# -.net
KiCad netlist of a schematic drawn in Altium Designer
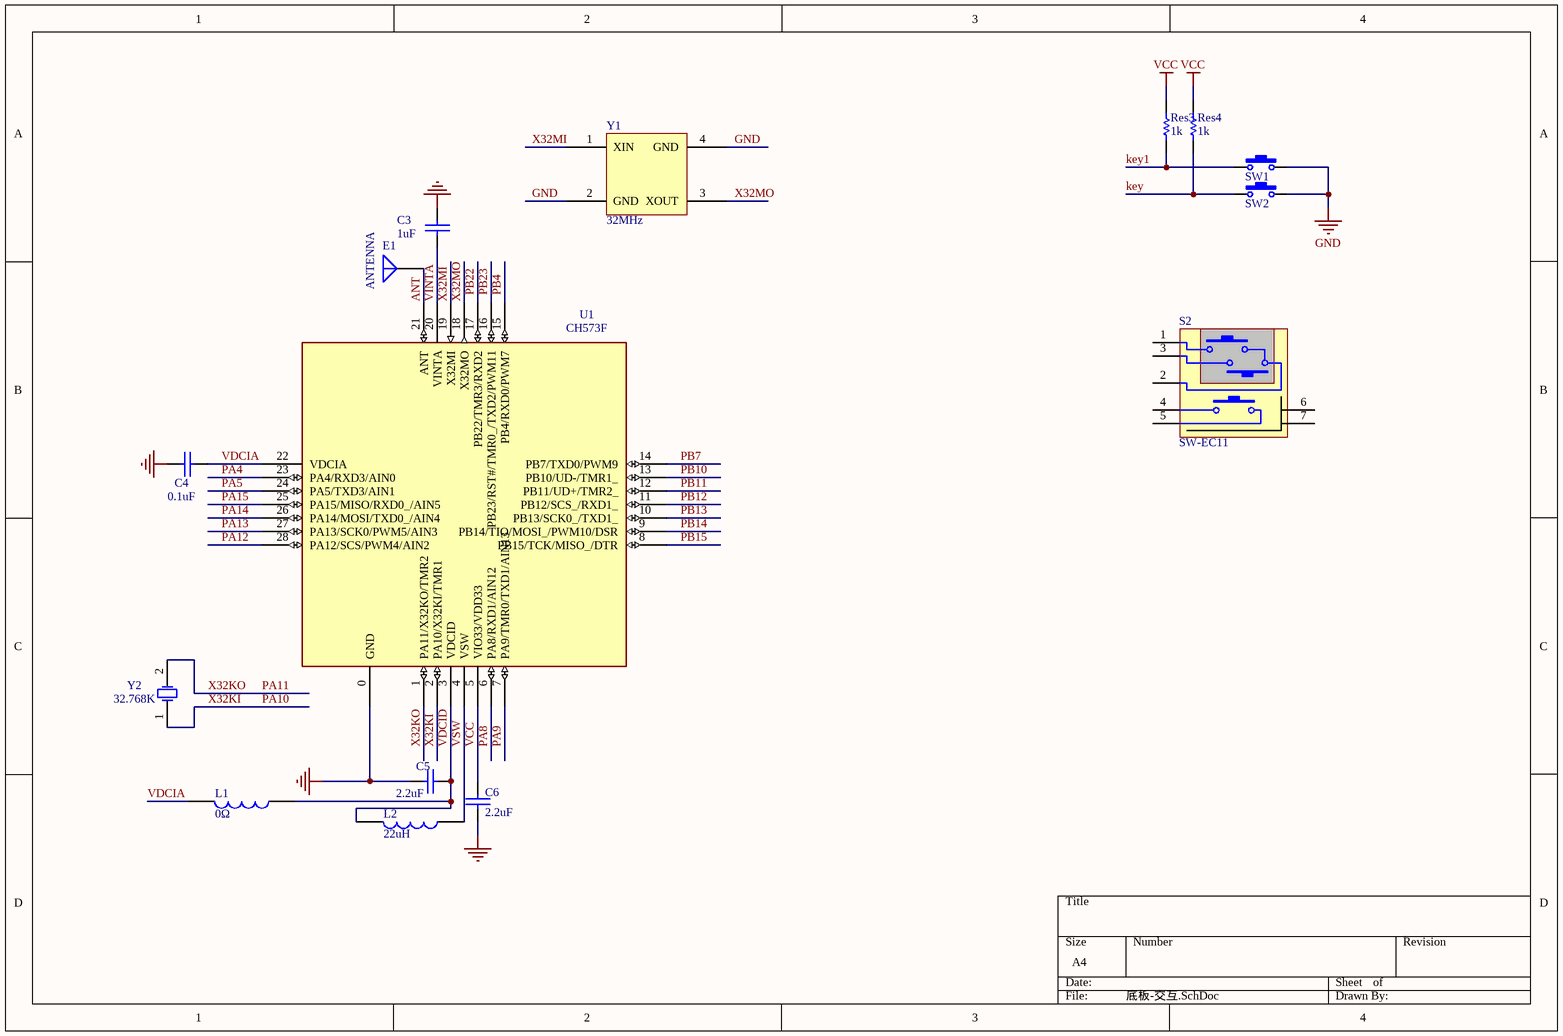
[diagram p0: 底板-交互.SchDoc]

(export (version "E")
  (design (tool "Eeschema 10.0.6"))
  (components
    (comp (ref "C3")
      (value "1uF")
      (footprint "MYPCB:0402")
      (description "Capacitor")
      (libsource (lib "*") (part "CAP"))
    )
    (comp (ref "C4")
      (value "0.1uF")
      (footprint "MYPCB:0402")
      (description "Capacitor")
      (libsource (lib "*") (part "CAP"))
    )
    (comp (ref "C5")
      (value "2.2uF")
      (footprint "MYPCB:0402")
      (description "Capacitor")
      (libsource (lib "*") (part "CAP"))
    )
    (comp (ref "C6")
      (value "2.2uF")
      (footprint "MYPCB:0402")
      (description "Capacitor")
      (libsource (lib "*") (part "CAP"))
    )
    (comp (ref "E1")
      (value "ANTENNA")
      (footprint "ANT-F-1-2.4G-1.6")
      (description "Generic Antenna")
      (libsource (lib "*") (part "ANTENNA"))
    )
    (comp (ref "L1") (value "0Ω") (footprint "0603") (libsource (lib "*") (part "INDUCTOR")))
    (comp (ref "L2") (value "22uH") (footprint "L2.2") (libsource (lib "*") (part "INDUCTOR")))
    (comp (ref "Res3") (value "1k") (footprint "0805R") (libsource (lib "电阻") (part "RES")))
    (comp (ref "Res4") (value "1k") (footprint "0805R") (libsource (lib "电阻") (part "RES")))
    (comp (ref "S2")
      (value "SW-EC11")
      (footprint "EC11")
      (description "旋转编码开关")
      (libsource (lib "0.7 - 常用按键-开关-蜂鸣器-电池-测试点") (part "SW-EC11"))
    )
    (comp (ref "SW1")
      (value "3x6x5")
      (footprint "SW 3*6*4.3-S-W")
      (description "3x6轻触开关")
      (libsource (lib "0.7 - 常用按键-开关-蜂鸣器-电池-测试点") (part "TSW 3x6"))
    )
    (comp (ref "SW2")
      (value "3x6x5")
      (footprint "SW 3*6*4.3-S-W")
      (description "3x6轻触开关")
      (libsource (lib "0.7 - 常用按键-开关-蜂鸣器-电池-测试点") (part "TSW 3x6"))
    )
    (comp (ref "U1")
      (value "CH573F")
      (footprint "QFN28_4X4")
      (description "RISC-V MCU with BLE/USB/ADC/SPI/4*UART")
      (libsource (lib "altium-import") (part "root_0_CH573F_"))
    )
    (comp (ref "Y1") (value "32MHz") (footprint "3225") (libsource (lib "wch_sch_others") (part "晶体")))
    (comp (ref "Y2")
      (value "32.768K")
      (footprint "fc-135")
      (description "Crystal Oscillator")
      (fields (field (name "PUBLISHER") "Altium Limited"))
      (libsource (lib "*") (part "XTAL"))
    )
  )
  (nets
    (net (code "1") (name "/ANT") (class "Default")
      (node (ref "E1") (pin "1") (pinfunction "A_1") (pintype "passive"))
      (node (ref "U1") (pin "21") (pinfunction "ANT_21") (pintype "bidirectional"))
    )
    (net (code "2") (name "/PA4") (class "Default")
      (node (ref "U1") (pin "23") (pinfunction "PA4/RXD3/AIN0_23") (pintype "bidirectional"))
    )
    (net (code "3") (name "/PA5") (class "Default")
      (node (ref "U1") (pin "24") (pinfunction "PA5/TXD3/AIN1_24") (pintype "bidirectional"))
    )
    (net (code "4") (name "/PA8") (class "Default")
      (node (ref "U1") (pin "6") (pinfunction "PA8/RXD1/AIN12_6") (pintype "bidirectional"))
    )
    (net (code "5") (name "/PA9") (class "Default")
      (node (ref "U1") (pin "7") (pinfunction "PA9/TMR0/TXD1/AIN13_7") (pintype "bidirectional"))
    )
    (net (code "6") (name "/PA10") (class "Default")
      (node (ref "U1") (pin "2") (pinfunction "PA10/X32KI/TMR1_2") (pintype "bidirectional"))
      (node (ref "Y2") (pin "1") (pinfunction "OSC1_1") (pintype "passive"))
    )
    (net (code "7") (name "/PA11") (class "Default")
      (node (ref "U1") (pin "1") (pinfunction "PA11/X32KO/TMR2_1") (pintype "bidirectional"))
      (node (ref "Y2") (pin "2") (pinfunction "OSC2_2") (pintype "passive"))
    )
    (net (code "8") (name "/PA12") (class "Default")
      (node (ref "U1") (pin "28") (pinfunction "PA12/SCS/PWM4/AIN2_28") (pintype "bidirectional"))
    )
    (net (code "9") (name "/PA13") (class "Default")
      (node (ref "U1") (pin "27") (pinfunction "PA13/SCK0/PWM5/AIN3_27") (pintype "bidirectional"))
    )
    (net (code "10") (name "/PA14") (class "Default")
      (node (ref "U1") (pin "26") (pinfunction "PA14/MOSI/TXD0_/AIN4_26") (pintype "bidirectional"))
    )
    (net (code "11") (name "/PA15") (class "Default")
      (node (ref "U1") (pin "25") (pinfunction "PA15/MISO/RXD0_/AIN5_25") (pintype "bidirectional"))
    )
    (net (code "12") (name "/PB4") (class "Default")
      (node (ref "U1") (pin "15") (pinfunction "PB4/RXD0/PWM7_15") (pintype "bidirectional"))
    )
    (net (code "13") (name "/PB7") (class "Default")
      (node (ref "U1") (pin "14") (pinfunction "PB7/TXD0/PWM9_14") (pintype "bidirectional"))
    )
    (net (code "14") (name "/PB10") (class "Default")
      (node (ref "U1") (pin "13") (pinfunction "PB10/UD-/TMR1__13") (pintype "bidirectional"))
    )
    (net (code "15") (name "/PB11") (class "Default")
      (node (ref "U1") (pin "12") (pinfunction "PB11/UD+/TMR2__12") (pintype "bidirectional"))
    )
    (net (code "16") (name "/PB12") (class "Default")
      (node (ref "U1") (pin "11") (pinfunction "PB12/SCS_/RXD1__11") (pintype "bidirectional"))
    )
    (net (code "17") (name "/PB13") (class "Default")
      (node (ref "U1") (pin "10") (pinfunction "PB13/SCK0_/TXD1__10") (pintype "bidirectional"))
    )
    (net (code "18") (name "/PB14") (class "Default")
      (node (ref "U1") (pin "9") (pinfunction "PB14/TIO/MOSI_/PWM10/DSR_9") (pintype "bidirectional"))
    )
    (net (code "19") (name "/PB15") (class "Default")
      (node (ref "U1") (pin "8") (pinfunction "PB15/TCK/MISO_/DTR_8") (pintype "bidirectional"))
    )
    (net (code "20") (name "/PB22") (class "Default")
      (node (ref "U1") (pin "17") (pinfunction "PB22/TMR3/RXD2_17") (pintype "bidirectional"))
    )
    (net (code "21") (name "/PB23") (class "Default")
      (node (ref "U1") (pin "16") (pinfunction "PB23/RST#/TMR0_/TXD2/PWM11_16") (pintype "bidirectional"))
    )
    (net (code "22") (name "/VDCIA") (class "Default")
      (node (ref "C4") (pin "1") (pinfunction "1_1") (pintype "passive"))
      (node (ref "L1") (pin "2") (pinfunction "2_2") (pintype "passive"))
      (node (ref "U1") (pin "22") (pinfunction "VDCIA_22") (pintype "power_in"))
    )
    (net (code "23") (name "/VDCID") (class "Default")
      (node (ref "C5") (pin "2") (pinfunction "2_2") (pintype "passive"))
      (node (ref "L1") (pin "1") (pinfunction "1_1") (pintype "passive"))
      (node (ref "L2") (pin "2") (pinfunction "2_2") (pintype "passive"))
      (node (ref "U1") (pin "3") (pinfunction "VDCID_3") (pintype "power_in"))
    )
    (net (code "24") (name "/VINTA") (class "Default")
      (node (ref "C3") (pin "1") (pinfunction "1_1") (pintype "passive"))
      (node (ref "U1") (pin "20") (pinfunction "VINTA_20") (pintype "power_in"))
    )
    (net (code "25") (name "/VSW") (class "Default")
      (node (ref "L2") (pin "1") (pinfunction "1_1") (pintype "passive"))
      (node (ref "U1") (pin "4") (pinfunction "VSW_4") (pintype "power_in"))
    )
    (net (code "26") (name "/X32MI") (class "Default")
      (node (ref "U1") (pin "19") (pinfunction "X32MI_19") (pintype "input"))
      (node (ref "Y1") (pin "1") (pinfunction "XIN_1") (pintype "passive"))
    )
    (net (code "27") (name "/X32MO") (class "Default")
      (node (ref "U1") (pin "18") (pinfunction "X32MO_18") (pintype "output"))
      (node (ref "Y1") (pin "3") (pinfunction "XOUT_3") (pintype "passive"))
    )
    (net (code "28") (name "/key") (class "Default")
      (node (ref "Res4") (pin "2") (pinfunction "2_2") (pintype "passive"))
      (node (ref "SW2") (pin "1") (pinfunction "1_1") (pintype "passive"))
    )
    (net (code "29") (name "/key1") (class "Default")
      (node (ref "Res3") (pin "2") (pinfunction "2_2") (pintype "passive"))
      (node (ref "SW1") (pin "1") (pinfunction "1_1") (pintype "passive"))
    )
    (net (code "30") (name "GND") (class "Default")
      (node (ref "C3") (pin "2") (pinfunction "2_2") (pintype "passive"))
      (node (ref "C4") (pin "2") (pinfunction "2_2") (pintype "passive"))
      (node (ref "C5") (pin "1") (pinfunction "1_1") (pintype "passive"))
      (node (ref "C6") (pin "1") (pinfunction "1_1") (pintype "passive"))
      (node (ref "SW1") (pin "2") (pinfunction "2_2") (pintype "passive"))
      (node (ref "SW2") (pin "2") (pinfunction "2_2") (pintype "passive"))
      (node (ref "U1") (pin "0") (pinfunction "GND_0") (pintype "power_in"))
      (node (ref "Y1") (pin "2") (pinfunction "GND_2") (pintype "passive"))
      (node (ref "Y1") (pin "4") (pinfunction "GND_4") (pintype "passive"))
    )
    (net (code "31") (name "VCC") (class "Default")
      (node (ref "C6") (pin "2") (pinfunction "2_2") (pintype "passive"))
      (node (ref "Res3") (pin "1") (pinfunction "1_1") (pintype "passive"))
      (node (ref "Res4") (pin "1") (pinfunction "1_1") (pintype "passive"))
      (node (ref "U1") (pin "5") (pinfunction "VIO33/VDD33_5") (pintype "power_in"))
    )
    (net (code "32") (name "unconnected-(S2-Pad1)") (class "Default")
      (node (ref "S2") (pin "1") (pinfunction "1_1") (pintype "passive"))
    )
    (net (code "33") (name "unconnected-(S2-Pad2)") (class "Default")
      (node (ref "S2") (pin "2") (pinfunction "2_2") (pintype "passive"))
    )
    (net (code "34") (name "unconnected-(S2-Pad3)") (class "Default")
      (node (ref "S2") (pin "3") (pinfunction "3_3") (pintype "passive"))
    )
    (net (code "35") (name "unconnected-(S2-Pad4)") (class "Default")
      (node (ref "S2") (pin "4") (pinfunction "4_4") (pintype "passive"))
    )
    (net (code "36") (name "unconnected-(S2-Pad5)") (class "Default")
      (node (ref "S2") (pin "5") (pinfunction "5_5") (pintype "passive"))
    )
    (net (code "37") (name "unconnected-(S2-Pad6)") (class "Default")
      (node (ref "S2") (pin "6") (pinfunction "6_6") (pintype "passive"))
    )
    (net (code "38") (name "unconnected-(S2-Pad7)") (class "Default")
      (node (ref "S2") (pin "7") (pinfunction "7_7") (pintype "passive"))
    )
  )
)
